# untitled.net
KiCad netlist of a schematic drawn in EAGLE
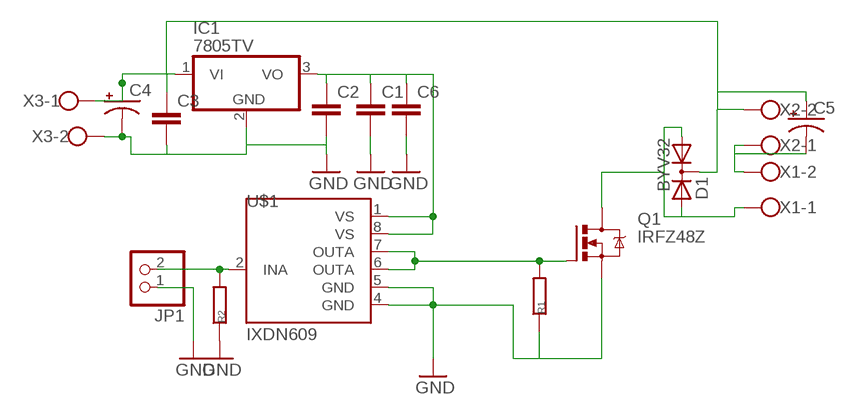
[diagram p0: schematic, sheet 1]

(export (version "E")
  (design (tool "Eeschema 10.0.6"))
  (components
    (comp (ref "C1")
      (value "CC0805")
      (footprint "eagle-import:C0805")
      (libsource (lib "eagle-import") (part "CC0805"))
    )
    (comp (ref "C2")
      (value "CC0805")
      (footprint "eagle-import:C0805")
      (libsource (lib "eagle-import") (part "CC0805"))
    )
    (comp (ref "C3")
      (value "CC0805")
      (footprint "eagle-import:C0805")
      (libsource (lib "eagle-import") (part "CC0805"))
    )
    (comp (ref "C4")
      (value "CAP_POLPTH4")
      (footprint "eagle-import:CPOL-RADIAL-1000UF-25V")
      (libsource (lib "eagle-import") (part "CAP_POLPTH4"))
    )
    (comp (ref "C5")
      (value "CAP_POLPTH4")
      (footprint "eagle-import:CPOL-RADIAL-1000UF-25V")
      (libsource (lib "eagle-import") (part "CAP_POLPTH4"))
    )
    (comp (ref "C6")
      (value "CC0805")
      (footprint "eagle-import:C0805")
      (libsource (lib "eagle-import") (part "CC0805"))
    )
    (comp (ref "D1")
      (value "BYV32")
      (footprint "eagle-import:TO220ABS")
      (libsource (lib "eagle-import") (part "BYV32"))
    )
    (comp (ref "IC1")
      (value "7805TV")
      (footprint "eagle-import:TO220V")
      (libsource (lib "eagle-import") (part "78TV05"))
    )
    (comp (ref "JP1")
      (value "PINHD-1X2")
      (footprint "eagle-import:1X02")
      (libsource (lib "eagle-import") (part "PINHD-1X2"))
    )
    (comp (ref "Q1")
      (value "IRFZ48Z")
      (footprint "eagle-import:TO220BH")
      (libsource (lib "eagle-import") (part "IRFZ48Z"))
    )
    (comp (ref "R1")
      (value "R0805")
      (footprint "eagle-import:R0805")
      (libsource (lib "eagle-import") (part "R0805"))
    )
    (comp (ref "R2")
      (value "R0805")
      (footprint "eagle-import:R0805")
      (libsource (lib "eagle-import") (part "R0805"))
    )
    (comp (ref "U$1")
      (value "IXDN609")
      (footprint "eagle-import:SO08")
      (libsource (lib "eagle-import") (part "IXDN609"))
    )
    (comp (ref "X1")
      (value "W237-102")
      (footprint "eagle-import:W237-102")
      (fields (field (name "MPN") "237-102"))
      (libsource (lib "eagle-import") (part "W237-102"))
    )
    (comp (ref "X2")
      (value "W237-102")
      (footprint "eagle-import:W237-102")
      (fields (field (name "MPN") "237-102"))
      (libsource (lib "eagle-import") (part "W237-102"))
    )
    (comp (ref "X3")
      (value "W237-102")
      (footprint "eagle-import:W237-102")
      (fields (field (name "MPN") "237-102"))
      (libsource (lib "eagle-import") (part "W237-102"))
    )
  )
  (nets
    (net (code "1") (name "GND") (class "Default")
      (node (ref "C1") (pin "2") (pinfunction "2_2") (pintype "passive"))
      (node (ref "C2") (pin "2") (pinfunction "2_2") (pintype "passive"))
      (node (ref "C3") (pin "2") (pinfunction "2_2") (pintype "passive"))
      (node (ref "C4") (pin "-") (pinfunction "-_-") (pintype "passive"))
      (node (ref "C6") (pin "2") (pinfunction "2_2") (pintype "passive"))
      (node (ref "IC1") (pin "2") (pinfunction "GND_2") (pintype "passive"))
      (node (ref "JP1") (pin "1") (pinfunction "1_1") (pintype "passive"))
      (node (ref "Q1") (pin "S") (pinfunction "S_S") (pintype "passive"))
      (node (ref "R1") (pin "1") (pinfunction "1_1") (pintype "passive"))
      (node (ref "R2") (pin "1") (pinfunction "1_1") (pintype "passive"))
      (node (ref "U$1") (pin "4") (pinfunction "GND_4") (pintype "power_in"))
      (node (ref "U$1") (pin "5") (pinfunction "GND_5") (pintype "power_in"))
      (node (ref "X3") (pin "2") (pinfunction "KL_2") (pintype "passive"))
    )
    (net (code "2") (name "Net-(IC1-VI)") (class "Default")
      (node (ref "C3") (pin "1") (pinfunction "1_1") (pintype "passive"))
      (node (ref "C4") (pin "+") (pinfunction "+_+") (pintype "passive"))
      (node (ref "C5") (pin "+") (pinfunction "+_+") (pintype "passive"))
      (node (ref "D1") (pin "C") (pinfunction "C_C") (pintype "passive"))
      (node (ref "IC1") (pin "1") (pinfunction "VI_1") (pintype "input"))
      (node (ref "X2") (pin "2") (pinfunction "KL_2") (pintype "passive"))
      (node (ref "X3") (pin "1") (pinfunction "KL_1") (pintype "passive"))
    )
    (net (code "3") (name "Net-(IC1-VO)") (class "Default")
      (node (ref "C1") (pin "1") (pinfunction "1_1") (pintype "passive"))
      (node (ref "C2") (pin "1") (pinfunction "1_1") (pintype "passive"))
      (node (ref "C6") (pin "1") (pinfunction "1_1") (pintype "passive"))
      (node (ref "IC1") (pin "3") (pinfunction "VO_3") (pintype "passive"))
      (node (ref "U$1") (pin "1") (pinfunction "VS_1") (pintype "power_in"))
      (node (ref "U$1") (pin "8") (pinfunction "VS_8") (pintype "power_in"))
    )
    (net (code "4") (name "Net-(Q1-PadG)") (class "Default")
      (node (ref "Q1") (pin "G") (pinfunction "G_G") (pintype "passive"))
      (node (ref "R1") (pin "2") (pinfunction "2_2") (pintype "passive"))
      (node (ref "U$1") (pin "6") (pinfunction "OUTA_6") (pintype "output"))
      (node (ref "U$1") (pin "7") (pinfunction "OUTA_7") (pintype "output"))
    )
    (net (code "5") (name "Net-(U$1-INA)") (class "Default")
      (node (ref "JP1") (pin "2") (pinfunction "2_2") (pintype "passive"))
      (node (ref "R2") (pin "2") (pinfunction "2_2") (pintype "passive"))
      (node (ref "U$1") (pin "2") (pinfunction "INA_2") (pintype "input"))
    )
    (net (code "6") (name "Net-(X1A-KL)") (class "Default")
      (node (ref "D1") (pin "A1") (pinfunction "A1_A1") (pintype "passive"))
      (node (ref "D1") (pin "A2") (pinfunction "A2_A2") (pintype "passive"))
      (node (ref "Q1") (pin "D") (pinfunction "D_D") (pintype "passive"))
      (node (ref "X1") (pin "1") (pinfunction "KL_1") (pintype "passive"))
    )
    (net (code "7") (name "Net-(X1B-KL)") (class "Default")
      (node (ref "C5") (pin "-") (pinfunction "-_-") (pintype "passive"))
      (node (ref "X1") (pin "2") (pinfunction "KL_2") (pintype "passive"))
      (node (ref "X2") (pin "1") (pinfunction "KL_1") (pintype "passive"))
    )
  )
)
